# WirelessDrivers.net
KiCad netlist of a schematic drawn in Altium Designer
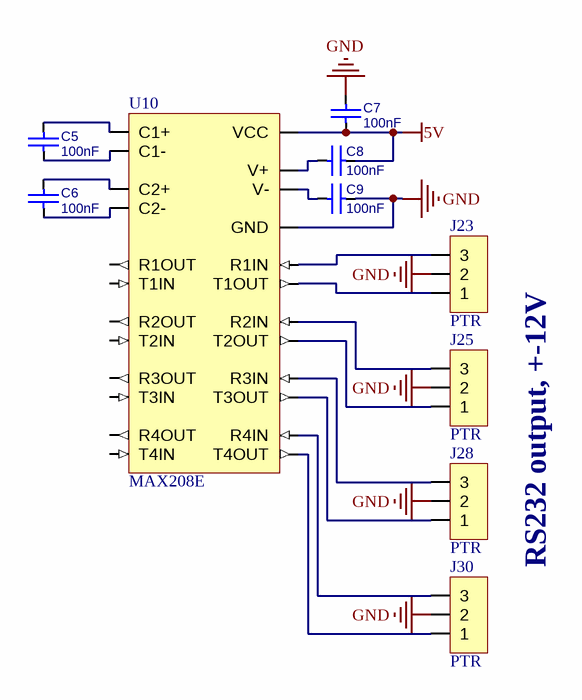
[diagram p0: WirelessDrivers.SchDoc]

(export (version "E")
  (design (tool "Eeschema 10.0.6"))
  (components
    (comp (ref "C5")
      (value "100nF")
      (footprint "0603")
      (description "Keramikkondensator 0603")
      (fields (field (name "CHANGED BY") "taalbiss"))
      (libsource (lib "CCE_Database_Libs") (part "C_Normal"))
    )
    (comp (ref "C6")
      (value "100nF")
      (footprint "0603")
      (description "Keramikkondensator 0603")
      (fields (field (name "CHANGED BY") "taalbiss"))
      (libsource (lib "CCE_Database_Libs") (part "C_Normal"))
    )
    (comp (ref "C7")
      (value "100nF")
      (footprint "0603")
      (description "Keramikkondensator 0603")
      (fields (field (name "CHANGED BY") "taalbiss"))
      (libsource (lib "CCE_Database_Libs") (part "C_Normal"))
    )
    (comp (ref "C8")
      (value "100nF")
      (footprint "0603")
      (description "Keramikkondensator 0603")
      (fields (field (name "CHANGED BY") "taalbiss"))
      (libsource (lib "CCE_Database_Libs") (part "C_Normal"))
    )
    (comp (ref "C9")
      (value "100nF")
      (footprint "0603")
      (description "Keramikkondensator 0603")
      (fields (field (name "CHANGED BY") "taalbiss"))
      (libsource (lib "CCE_Database_Libs") (part "C_Normal"))
    )
    (comp (ref "J23") (value "PTR") (footprint "PTR_1X3") (libsource (lib "UAV") (part "Header_1x3")))
    (comp (ref "J25") (value "PTR") (footprint "PTR_1X3") (libsource (lib "UAV") (part "Header_1x3")))
    (comp (ref "J28") (value "PTR") (footprint "PTR_1X3") (libsource (lib "UAV") (part "Header_1x3")))
    (comp (ref "J30") (value "PTR") (footprint "PTR_1X3") (libsource (lib "UAV") (part "Header_1x3")))
    (comp (ref "U10") (value "MAX208E") (footprint "UAV:SSOP24") (libsource (lib "UAV") (part "MAX208E")))
  )
  (nets
    (net (code "1") (name "5V") (class "Default")
      (node (ref "C7") (pin "1") (pinfunction "1_1") (pintype "passive"))
      (node (ref "C8") (pin "1") (pinfunction "1_1") (pintype "passive"))
      (node (ref "U10") (pin "9") (pinfunction "VCC_9") (pintype "passive"))
    )
    (net (code "2") (name "GND") (class "Default")
      (node (ref "C7") (pin "2") (pinfunction "2_2") (pintype "passive"))
      (node (ref "C9") (pin "1") (pinfunction "1_1") (pintype "passive"))
      (node (ref "J23") (pin "2") (pinfunction "2_2") (pintype "passive"))
      (node (ref "J25") (pin "2") (pinfunction "2_2") (pintype "passive"))
      (node (ref "J28") (pin "2") (pinfunction "2_2") (pintype "passive"))
      (node (ref "J30") (pin "2") (pinfunction "2_2") (pintype "passive"))
      (node (ref "U10") (pin "8") (pinfunction "GND_8") (pintype "passive"))
    )
    (net (code "3") (name "Net-(U10-C1+)") (class "Default")
      (node (ref "C5") (pin "2") (pinfunction "2_2") (pintype "passive"))
      (node (ref "U10") (pin "10") (pinfunction "C1+_10") (pintype "passive"))
    )
    (net (code "4") (name "Net-(U10-C1-)") (class "Default")
      (node (ref "C5") (pin "1") (pinfunction "1_1") (pintype "passive"))
      (node (ref "U10") (pin "12") (pinfunction "C1-_12") (pintype "passive"))
    )
    (net (code "5") (name "Net-(U10-C2+)") (class "Default")
      (node (ref "C6") (pin "2") (pinfunction "2_2") (pintype "passive"))
      (node (ref "U10") (pin "13") (pinfunction "C2+_13") (pintype "passive"))
    )
    (net (code "6") (name "Net-(U10-C2-)") (class "Default")
      (node (ref "C6") (pin "1") (pinfunction "1_1") (pintype "passive"))
      (node (ref "U10") (pin "14") (pinfunction "C2-_14") (pintype "passive"))
    )
    (net (code "7") (name "Net-(U10-R1IN)") (class "Default")
      (node (ref "J23") (pin "3") (pinfunction "3_3") (pintype "passive"))
      (node (ref "U10") (pin "7") (pinfunction "R1IN_7") (pintype "input"))
    )
    (net (code "8") (name "Net-(U10-R2IN)") (class "Default")
      (node (ref "J25") (pin "3") (pinfunction "3_3") (pintype "passive"))
      (node (ref "U10") (pin "3") (pinfunction "R2IN_3") (pintype "input"))
    )
    (net (code "9") (name "Net-(U10-R3IN)") (class "Default")
      (node (ref "J28") (pin "3") (pinfunction "3_3") (pintype "passive"))
      (node (ref "U10") (pin "23") (pinfunction "R3IN_23") (pintype "input"))
    )
    (net (code "10") (name "Net-(U10-R4IN)") (class "Default")
      (node (ref "J30") (pin "3") (pinfunction "3_3") (pintype "passive"))
      (node (ref "U10") (pin "16") (pinfunction "R4IN_16") (pintype "input"))
    )
    (net (code "11") (name "Net-(U10-T1OUT)") (class "Default")
      (node (ref "J23") (pin "1") (pinfunction "1_1") (pintype "passive"))
      (node (ref "U10") (pin "2") (pinfunction "T1OUT_2") (pintype "output"))
    )
    (net (code "12") (name "Net-(U10-T2OUT)") (class "Default")
      (node (ref "J25") (pin "1") (pinfunction "1_1") (pintype "passive"))
      (node (ref "U10") (pin "1") (pinfunction "T2OUT_1") (pintype "output"))
    )
    (net (code "13") (name "Net-(U10-T3OUT)") (class "Default")
      (node (ref "J28") (pin "1") (pinfunction "1_1") (pintype "passive"))
      (node (ref "U10") (pin "24") (pinfunction "T3OUT_24") (pintype "output"))
    )
    (net (code "14") (name "Net-(U10-T4OUT)") (class "Default")
      (node (ref "J30") (pin "1") (pinfunction "1_1") (pintype "passive"))
      (node (ref "U10") (pin "20") (pinfunction "T4OUT_20") (pintype "output"))
    )
    (net (code "15") (name "Net-(U10-V+)") (class "Default")
      (node (ref "C8") (pin "2") (pinfunction "2_2") (pintype "passive"))
      (node (ref "U10") (pin "11") (pinfunction "V+_11") (pintype "passive"))
    )
    (net (code "16") (name "Net-(U10-V-)") (class "Default")
      (node (ref "C9") (pin "2") (pinfunction "2_2") (pintype "passive"))
      (node (ref "U10") (pin "15") (pinfunction "V-_15") (pintype "passive"))
    )
    (net (code "17") (name "unconnected-(U10-R1OUT-Pad6)") (class "Default")
      (node (ref "U10") (pin "6") (pinfunction "R1OUT_6") (pintype "output"))
    )
    (net (code "18") (name "unconnected-(U10-R2OUT-Pad4)") (class "Default")
      (node (ref "U10") (pin "4") (pinfunction "R2OUT_4") (pintype "output"))
    )
    (net (code "19") (name "unconnected-(U10-R3OUT-Pad22)") (class "Default")
      (node (ref "U10") (pin "22") (pinfunction "R3OUT_22") (pintype "output"))
    )
    (net (code "20") (name "unconnected-(U10-R4OUT-Pad17)") (class "Default")
      (node (ref "U10") (pin "17") (pinfunction "R4OUT_17") (pintype "output"))
    )
    (net (code "21") (name "unconnected-(U10-T1IN-Pad5)") (class "Default")
      (node (ref "U10") (pin "5") (pinfunction "T1IN_5") (pintype "input"))
    )
    (net (code "22") (name "unconnected-(U10-T2IN-Pad18)") (class "Default")
      (node (ref "U10") (pin "18") (pinfunction "T2IN_18") (pintype "input"))
    )
    (net (code "23") (name "unconnected-(U10-T3IN-Pad19)") (class "Default")
      (node (ref "U10") (pin "19") (pinfunction "T3IN_19") (pintype "input"))
    )
    (net (code "24") (name "unconnected-(U10-T4IN-Pad21)") (class "Default")
      (node (ref "U10") (pin "21") (pinfunction "T4IN_21") (pintype "input"))
    )
  )
)
